# main.net
KiCad netlist of a schematic drawn in EAGLE
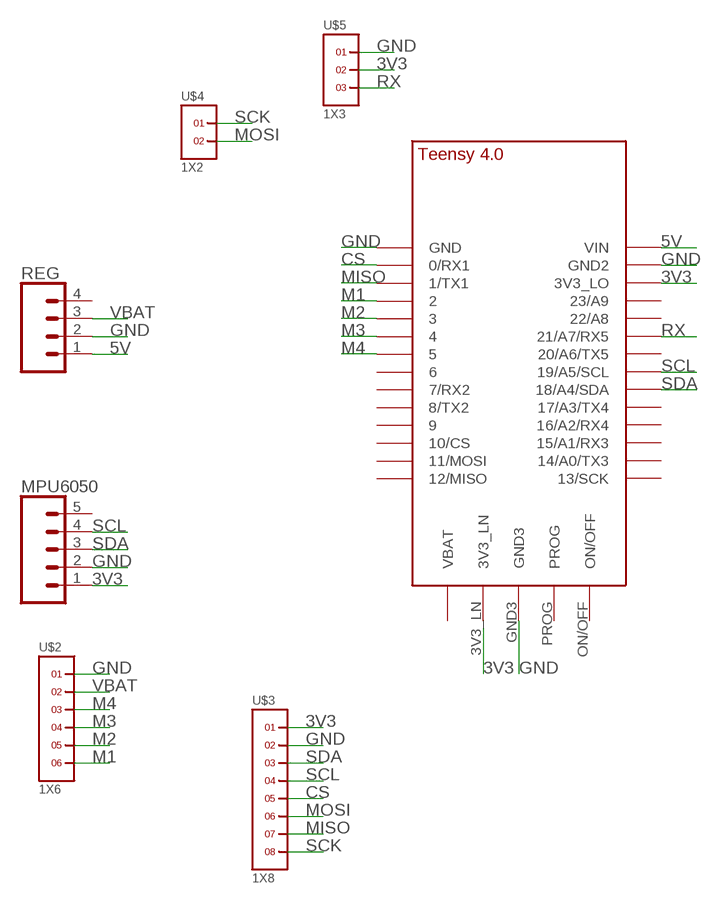
[diagram p0: schematic, sheet 1]

(export (version "E")
  (design (tool "Eeschema 10.0.6"))
  (components
    (comp (ref "MPU6050")
      (value "CONN_05NO_SILK")
      (footprint "eagle-import:1X05_NO_SILK")
      (libsource (lib "eagle-import") (part "CONN_05NO_SILK"))
    )
    (comp (ref "REG")
      (value "CONN_041X04_NO_SILK")
      (footprint "eagle-import:1X04_NO_SILK")
      (libsource (lib "eagle-import") (part "CONN_041X04_NO_SILK"))
    )
    (comp (ref "U$1")
      (value "TEENSY_4.0")
      (footprint "eagle-import:TEENSY_4.0")
      (libsource (lib "eagle-import") (part "TEENSY_4.0"))
    )
    (comp (ref "U$2")
      (value "1X6")
      (footprint "eagle-import:1X6")
      (libsource (lib "eagle-import") (part "1X6"))
    )
    (comp (ref "U$3")
      (value "1X8")
      (footprint "eagle-import:1X8")
      (libsource (lib "eagle-import") (part "1X8"))
    )
    (comp (ref "U$4")
      (value "1X2")
      (footprint "eagle-import:1X2")
      (libsource (lib "eagle-import") (part "1X2"))
    )
    (comp (ref "U$5")
      (value "1X3")
      (footprint "eagle-import:1X3")
      (libsource (lib "eagle-import") (part "1X3"))
    )
  )
  (nets
    (net (code "1") (name "/3V3") (class "Default")
      (node (ref "MPU6050") (pin "1") (pinfunction "1_1") (pintype "passive"))
      (node (ref "U$1") (pin "3V3_LN") (pinfunction "3V3_LN_3V3_LN") (pintype "bidirectional"))
      (node (ref "U$1") (pin "3V3_LO") (pinfunction "3V3_LO_3V3_LO") (pintype "bidirectional"))
      (node (ref "U$3") (pin "1") (pinfunction "1_1") (pintype "bidirectional"))
      (node (ref "U$5") (pin "2") (pinfunction "2_2") (pintype "bidirectional"))
    )
    (net (code "2") (name "/5V") (class "Default")
      (node (ref "REG") (pin "1") (pinfunction "1_1") (pintype "passive"))
      (node (ref "U$1") (pin "VIN") (pinfunction "VIN_VIN") (pintype "bidirectional"))
    )
    (net (code "3") (name "/CS") (class "Default")
      (node (ref "U$1") (pin "0/RX") (pinfunction "0/RX1_0/RX") (pintype "bidirectional"))
      (node (ref "U$3") (pin "5") (pinfunction "5_5") (pintype "bidirectional"))
    )
    (net (code "4") (name "/GND") (class "Default")
      (node (ref "MPU6050") (pin "2") (pinfunction "2_2") (pintype "passive"))
      (node (ref "REG") (pin "2") (pinfunction "2_2") (pintype "passive"))
      (node (ref "U$1") (pin "GND") (pinfunction "GND_GND") (pintype "bidirectional"))
      (node (ref "U$1") (pin "GND2") (pinfunction "GND2_GND2") (pintype "bidirectional"))
      (node (ref "U$1") (pin "GND3") (pinfunction "GND3_GND3") (pintype "bidirectional"))
      (node (ref "U$2") (pin "1") (pinfunction "1_1") (pintype "bidirectional"))
      (node (ref "U$3") (pin "2") (pinfunction "2_2") (pintype "bidirectional"))
      (node (ref "U$5") (pin "1") (pinfunction "1_1") (pintype "bidirectional"))
    )
    (net (code "5") (name "/M1") (class "Default")
      (node (ref "U$1") (pin "2") (pinfunction "2_2") (pintype "bidirectional"))
      (node (ref "U$2") (pin "6") (pinfunction "6_6") (pintype "bidirectional"))
    )
    (net (code "6") (name "/M2") (class "Default")
      (node (ref "U$1") (pin "3/CANTX") (pinfunction "3_3/CANTX") (pintype "bidirectional"))
      (node (ref "U$2") (pin "5") (pinfunction "5_5") (pintype "bidirectional"))
    )
    (net (code "7") (name "/M3") (class "Default")
      (node (ref "U$1") (pin "4/CANRX") (pinfunction "4_4/CANRX") (pintype "bidirectional"))
      (node (ref "U$2") (pin "4") (pinfunction "4_4") (pintype "bidirectional"))
    )
    (net (code "8") (name "/M4") (class "Default")
      (node (ref "U$1") (pin "5") (pinfunction "5_5") (pintype "bidirectional"))
      (node (ref "U$2") (pin "3") (pinfunction "3_3") (pintype "bidirectional"))
    )
    (net (code "9") (name "/MISO") (class "Default")
      (node (ref "U$1") (pin "1/TX") (pinfunction "1/TX1_1/TX") (pintype "bidirectional"))
      (node (ref "U$3") (pin "7") (pinfunction "7_7") (pintype "bidirectional"))
    )
    (net (code "10") (name "/MOSI") (class "Default")
      (node (ref "U$3") (pin "6") (pinfunction "6_6") (pintype "bidirectional"))
      (node (ref "U$4") (pin "2") (pinfunction "2_2") (pintype "bidirectional"))
    )
    (net (code "11") (name "/RX") (class "Default")
      (node (ref "U$1") (pin "21/A7") (pinfunction "21/A7/RX5_21/A7") (pintype "bidirectional"))
      (node (ref "U$5") (pin "3") (pinfunction "3_3") (pintype "bidirectional"))
    )
    (net (code "12") (name "/SCK") (class "Default")
      (node (ref "U$3") (pin "8") (pinfunction "8_8") (pintype "bidirectional"))
      (node (ref "U$4") (pin "1") (pinfunction "1_1") (pintype "bidirectional"))
    )
    (net (code "13") (name "/SCL") (class "Default")
      (node (ref "MPU6050") (pin "4") (pinfunction "4_4") (pintype "passive"))
      (node (ref "U$1") (pin "19/A5/SCL") (pinfunction "19/A5/SCL_19/A5/SCL") (pintype "bidirectional"))
      (node (ref "U$3") (pin "4") (pinfunction "4_4") (pintype "bidirectional"))
    )
    (net (code "14") (name "/SDA") (class "Default")
      (node (ref "MPU6050") (pin "3") (pinfunction "3_3") (pintype "passive"))
      (node (ref "U$1") (pin "18/A4/SDA") (pinfunction "18/A4/SDA_18/A4/SDA") (pintype "bidirectional"))
      (node (ref "U$3") (pin "3") (pinfunction "3_3") (pintype "bidirectional"))
    )
    (net (code "15") (name "/VBAT") (class "Default")
      (node (ref "REG") (pin "3") (pinfunction "3_3") (pintype "passive"))
      (node (ref "U$2") (pin "2") (pinfunction "2_2") (pintype "bidirectional"))
    )
    (net (code "16") (name "unconnected-(MPU6050-Pad5)") (class "Default")
      (node (ref "MPU6050") (pin "5") (pinfunction "5_5") (pintype "passive"))
    )
    (net (code "17") (name "unconnected-(REG-Pad4)") (class "Default")
      (node (ref "REG") (pin "4") (pinfunction "4_4") (pintype "passive"))
    )
    (net (code "18") (name "unconnected-(U$1-7{slash}RX2-Pad7)") (class "Default")
      (node (ref "U$1") (pin "7") (pinfunction "7/RX2_7") (pintype "bidirectional"))
    )
    (net (code "19") (name "unconnected-(U$1-8{slash}TX2-Pad8)") (class "Default")
      (node (ref "U$1") (pin "8") (pinfunction "8/TX2_8") (pintype "bidirectional"))
    )
    (net (code "20") (name "unconnected-(U$1-9-Pad9{slash}CS)") (class "Default")
      (node (ref "U$1") (pin "9/CS") (pinfunction "9_9/CS") (pintype "bidirectional"))
    )
    (net (code "21") (name "unconnected-(U$1-14{slash}A0{slash}TX3-Pad14{slash}A0)") (class "Default")
      (node (ref "U$1") (pin "14/A0") (pinfunction "14/A0/TX3_14/A0") (pintype "bidirectional"))
    )
    (net (code "22") (name "unconnected-(U$1-15{slash}A1{slash}RX3-Pad15{slash}A1)") (class "Default")
      (node (ref "U$1") (pin "15/A1") (pinfunction "15/A1/RX3_15/A1") (pintype "bidirectional"))
    )
    (net (code "23") (name "unconnected-(U$1-16{slash}A2{slash}RX4-Pad16{slash}A2)") (class "Default")
      (node (ref "U$1") (pin "16/A2") (pinfunction "16/A2/RX4_16/A2") (pintype "bidirectional"))
    )
    (net (code "24") (name "unconnected-(U$1-17{slash}A3{slash}TX4-Pad17{slash}A3)") (class "Default")
      (node (ref "U$1") (pin "17/A3") (pinfunction "17/A3/TX4_17/A3") (pintype "bidirectional"))
    )
    (net (code "25") (name "unconnected-(U$1-20{slash}A6{slash}TX5-Pad20{slash}A6)") (class "Default")
      (node (ref "U$1") (pin "20/A6") (pinfunction "20/A6/TX5_20/A6") (pintype "bidirectional"))
    )
    (net (code "26") (name "unconnected-(U$1-Pad6)") (class "Default")
      (node (ref "U$1") (pin "6") (pinfunction "6_6") (pintype "bidirectional"))
    )
    (net (code "27") (name "unconnected-(U$1-Pad10{slash}CS)") (class "Default")
      (node (ref "U$1") (pin "10/CS") (pinfunction "10/CS_10/CS") (pintype "bidirectional"))
    )
    (net (code "28") (name "unconnected-(U$1-Pad11{slash}MOSI)") (class "Default")
      (node (ref "U$1") (pin "11/MOSI") (pinfunction "11/MOSI_11/MOSI") (pintype "bidirectional"))
    )
    (net (code "29") (name "unconnected-(U$1-Pad12{slash}MISO)") (class "Default")
      (node (ref "U$1") (pin "12/MISO") (pinfunction "12/MISO_12/MISO") (pintype "bidirectional"))
    )
    (net (code "30") (name "unconnected-(U$1-Pad13{slash}SCK)") (class "Default")
      (node (ref "U$1") (pin "13/SCK") (pinfunction "13/SCK_13/SCK") (pintype "bidirectional"))
    )
    (net (code "31") (name "unconnected-(U$1-Pad22{slash}A8)") (class "Default")
      (node (ref "U$1") (pin "22/A8") (pinfunction "22/A8_22/A8") (pintype "bidirectional"))
    )
    (net (code "32") (name "unconnected-(U$1-Pad23{slash}A9)") (class "Default")
      (node (ref "U$1") (pin "23/A9") (pinfunction "23/A9_23/A9") (pintype "bidirectional"))
    )
    (net (code "33") (name "unconnected-(U$1-PadON{slash}OFF)") (class "Default")
      (node (ref "U$1") (pin "ON/OFF") (pinfunction "ON/OFF_ON/OFF") (pintype "bidirectional"))
    )
    (net (code "34") (name "unconnected-(U$1-PadPROG)") (class "Default")
      (node (ref "U$1") (pin "PROG") (pinfunction "PROG_PROG") (pintype "bidirectional"))
    )
    (net (code "35") (name "unconnected-(U$1-VBAT-PadVBAT\\)") (class "Default")
      (node (ref "U$1") (pin "VBAT\\") (pinfunction "VBAT_VBAT\\") (pintype "bidirectional"))
    )
  )
)
